# LEDLamp.net
KiCad netlist of a schematic drawn in EAGLE
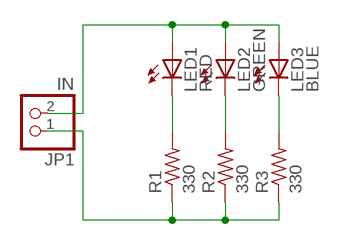
[diagram p0: schematic, sheet 1]

(export (version "E")
  (design (tool "Eeschema 10.0.6"))
  (components
    (comp (ref "JP1")
      (value "IN")
      (footprint "eagle-import:1X02")
      (libsource (lib "eagle-import") (part "PINHD-1X2"))
    )
    (comp (ref "LED1")
      (value "RED")
      (footprint "eagle-import:LED5MM")
      (libsource (lib "eagle-import") (part "LED5MM"))
    )
    (comp (ref "LED2")
      (value "GREEN")
      (footprint "eagle-import:LED5MM")
      (libsource (lib "eagle-import") (part "LED5MM"))
    )
    (comp (ref "LED3")
      (value "BLUE")
      (footprint "eagle-import:LED5MM")
      (libsource (lib "eagle-import") (part "LED5MM"))
    )
    (comp (ref "R1")
      (value "330")
      (footprint "eagle-import:0204_7")
      (libsource (lib "eagle-import") (part "R-US_0204/7"))
    )
    (comp (ref "R2")
      (value "330")
      (footprint "eagle-import:0204_7")
      (libsource (lib "eagle-import") (part "R-US_0204/7"))
    )
    (comp (ref "R3")
      (value "330")
      (footprint "eagle-import:0204_7")
      (libsource (lib "eagle-import") (part "R-US_0204/7"))
    )
  )
  (nets
    (net (code "1") (name "Net-(JP1-Pad1)") (class "Default")
      (node (ref "JP1") (pin "1") (pinfunction "1_1") (pintype "passive"))
      (node (ref "R1") (pin "1") (pinfunction "1_1") (pintype "passive"))
      (node (ref "R2") (pin "1") (pinfunction "1_1") (pintype "passive"))
      (node (ref "R3") (pin "1") (pinfunction "1_1") (pintype "passive"))
    )
    (net (code "2") (name "Net-(JP1-Pad2)") (class "Default")
      (node (ref "JP1") (pin "2") (pinfunction "2_2") (pintype "passive"))
      (node (ref "LED1") (pin "A") (pinfunction "A_A") (pintype "passive"))
      (node (ref "LED2") (pin "A") (pinfunction "A_A") (pintype "passive"))
      (node (ref "LED3") (pin "A") (pinfunction "A_A") (pintype "passive"))
    )
    (net (code "3") (name "Net-(LED1-C)") (class "Default")
      (node (ref "LED1") (pin "K") (pinfunction "C_K") (pintype "passive"))
      (node (ref "R1") (pin "2") (pinfunction "2_2") (pintype "passive"))
    )
    (net (code "4") (name "Net-(LED2-C)") (class "Default")
      (node (ref "LED2") (pin "K") (pinfunction "C_K") (pintype "passive"))
      (node (ref "R2") (pin "2") (pinfunction "2_2") (pintype "passive"))
    )
    (net (code "5") (name "Net-(LED3-C)") (class "Default")
      (node (ref "LED3") (pin "K") (pinfunction "C_K") (pintype "passive"))
      (node (ref "R3") (pin "2") (pinfunction "2_2") (pintype "passive"))
    )
  )
)
